# Cam_control.net
KiCad netlist of a schematic drawn in Altium Designer
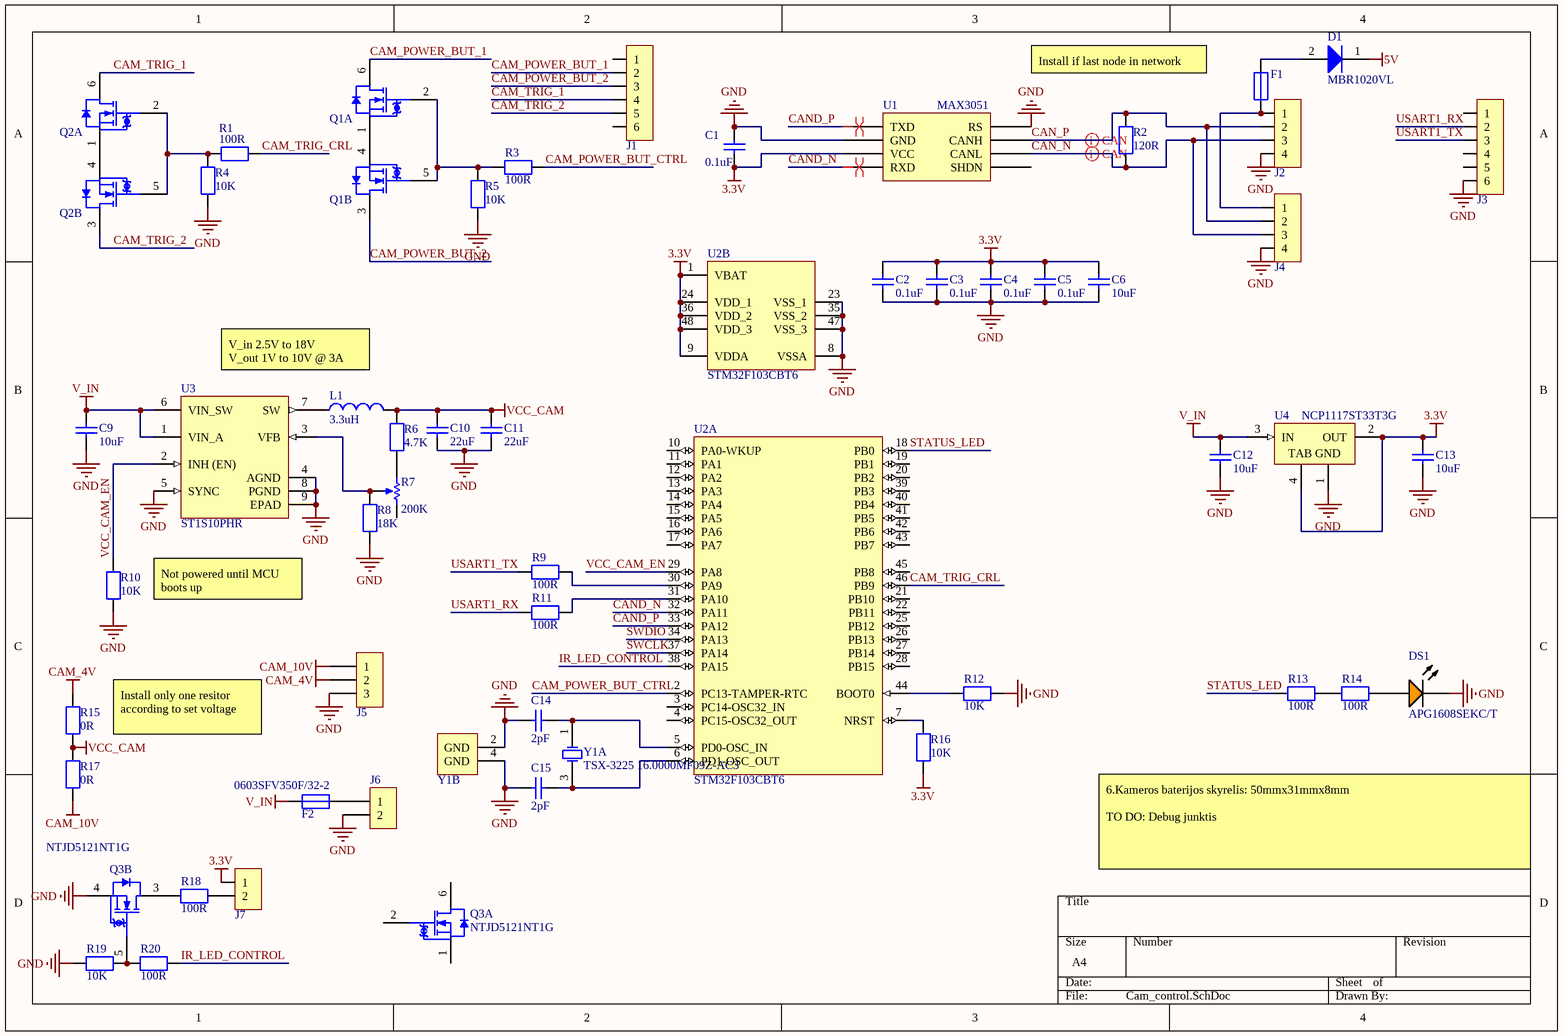
[diagram p0: Cam_control.SchDoc]

(export (version "E")
  (design (tool "Eeschema 10.0.6"))
  (components
    (comp (ref "C1")
      (value "0.1uF")
      (footprint "0603_CAP")
      (fields (field (name "Comment") "Capacitor"))
      (libsource (lib "Passive_comp") (part "Capacitor"))
    )
    (comp (ref "C2")
      (value "0.1uF")
      (footprint "0603_CAP")
      (fields (field (name "Comment") "Capacitor"))
      (libsource (lib "Passive_comp") (part "Capacitor"))
    )
    (comp (ref "C3")
      (value "0.1uF")
      (footprint "0603_CAP")
      (fields (field (name "Comment") "Capacitor"))
      (libsource (lib "Passive_comp") (part "Capacitor"))
    )
    (comp (ref "C4")
      (value "0.1uF")
      (footprint "0603_CAP")
      (fields (field (name "Comment") "Capacitor"))
      (libsource (lib "Passive_comp") (part "Capacitor"))
    )
    (comp (ref "C5")
      (value "0.1uF")
      (footprint "0603_CAP")
      (fields (field (name "Comment") "Capacitor"))
      (libsource (lib "Passive_comp") (part "Capacitor"))
    )
    (comp (ref "C6")
      (value "10uF")
      (footprint "1206_CAP")
      (fields (field (name "Comment") "Capacitor"))
      (libsource (lib "Passive_comp") (part "Capacitor"))
    )
    (comp (ref "C9")
      (value "10uF")
      (footprint "1206_CAP")
      (fields (field (name "Comment") "Capacitor"))
      (libsource (lib "Passive_comp") (part "Capacitor"))
    )
    (comp (ref "C10")
      (value "22uF")
      (footprint "0805_CAP")
      (fields (field (name "Comment") "Capacitor"))
      (libsource (lib "Passive_comp") (part "Capacitor"))
    )
    (comp (ref "C11")
      (value "22uF")
      (footprint "0805_CAP")
      (fields (field (name "Comment") "Capacitor"))
      (libsource (lib "Passive_comp") (part "Capacitor"))
    )
    (comp (ref "C12")
      (value "10uF")
      (footprint "1206_CAP")
      (fields (field (name "Comment") "Capacitor"))
      (libsource (lib "Passive_comp") (part "Capacitor"))
    )
    (comp (ref "C13")
      (value "10uF")
      (footprint "1206_CAP")
      (fields (field (name "Comment") "Capacitor"))
      (libsource (lib "Passive_comp") (part "Capacitor"))
    )
    (comp (ref "C14")
      (value "2pF")
      (footprint "0603_CAP")
      (fields (field (name "Comment") "Capacitor"))
      (libsource (lib "Passive_comp") (part "Capacitor"))
    )
    (comp (ref "C15")
      (value "2pF")
      (footprint "0603_CAP")
      (fields (field (name "Comment") "Capacitor"))
      (libsource (lib "Passive_comp") (part "Capacitor"))
    )
    (comp (ref "D1")
      (value "MBR1020VL")
      (footprint "SOD-123-2")
      (libsource (lib "Passive_comp") (part "Diode"))
    )
    (comp (ref "DS1")
      (value "APG1608SEKC/T")
      (footprint "KING-LED0603-25-ORANGE_V")
      (description "LED, SMT, 0603(1608), 0.25mm Tthickness, Super Bright Orange")
      (libsource (lib "Altium Content Vault") (part "KING-LED_ORANGE_A1K2-2"))
    )
    (comp (ref "F1") (value "Fuse") (footprint "0603_RES") (libsource (lib "Passive_comp") (part "Fuse")))
    (comp (ref "F2") (value "0603SFV350F/32-2") (footprint "0603_RES") (libsource (lib "") (part "Fuse_1")))
    (comp (ref "J1")
      (value "DF13-6P\n1.25mm Pitch Miniature Crimping Connector.")
      (footprint "DF13-6P-1.25DS")
      (libsource (lib "df13") (part "DF13-6P-1.25DS"))
    )
    (comp (ref "J2")
      (value "DF13-4P\n1.25mm Pitch Miniature Crimping Connector.")
      (footprint "DF13-4P-1.25DS")
      (libsource (lib "df13") (part "DF13-4P-1.25DS"))
    )
    (comp (ref "J3")
      (value "DF13-6P\n1.25mm Pitch Miniature Crimping Connector.")
      (footprint "DF13-6P-1.25DS")
      (libsource (lib "df13") (part "DF13-6P-1.25DS"))
    )
    (comp (ref "J4")
      (value "DF13-4P\n1.25mm Pitch Miniature Crimping Connector.")
      (footprint "DF13-4P-1.25DS")
      (libsource (lib "df13") (part "DF13-4P-1.25DS"))
    )
    (comp (ref "J5")
      (value "Molex - Micro-Fit 3.0 Series connector,  3.00mm (0.118\") pitch header, 3 positions.")
      (footprint "43650-0300")
      (libsource (lib "molex-micro-fit-3.0") (part "HEADER_POS3_?43650-0300"))
    )
    (comp (ref "J6")
      (value "Micro-Fit 3.0, 3.00mm pitch header")
      (footprint "43650-0200")
      (libsource (lib "con-molex-micro-fit-3_0") (part "HEADER_POS2_?43650-0200"))
    )
    (comp (ref "J7")
      (value "DF13-2P\n1.25mm Pitch Miniature Crimping Connector.")
      (footprint "DF13-2P-1.25DS")
      (libsource (lib "con-hirose-df13") (part "DF13-2P-1.25DS"))
    )
    (comp (ref "L1")
      (value "3.3uH")
      (footprint "ASPI0530")
      (fields (field (name "Comment") "Inductor"))
      (libsource (lib "Passive_comp") (part "Inductor"))
    )
    (comp (ref "Q1")
      (value "NTJD5121NT1G")
      (footprint "ONSC-SC70-6-419B-02_V")
      (description "Power MOSFET, 60 V, 295 mA, Dual N-Channel with ESD Protection, 6-Pin SC70, Pb-Free, Tape and Reel")
      (fields (field (name "MANUFACTURER") "On Semiconductor"))
      (libsource (lib "Altium Content Vault") (part "CMP-1058-00623-1"))
    )
    (comp (ref "Q2")
      (value "NTJD5121NT1G")
      (footprint "ONSC-SC70-6-419B-02_V")
      (description "Power MOSFET, 60 V, 295 mA, Dual N-Channel with ESD Protection, 6-Pin SC70, Pb-Free, Tape and Reel")
      (fields (field (name "MANUFACTURER") "On Semiconductor"))
      (libsource (lib "Altium Content Vault") (part "CMP-1058-00623-1"))
    )
    (comp (ref "Q3")
      (value "NTJD5121NT1G")
      (footprint "ONSC-SC70-6-419B-02_V")
      (description "Power MOSFET, 60 V, 295 mA, Dual N-Channel with ESD Protection, 6-Pin SC70, Pb-Free, Tape and Reel")
      (fields (field (name "MANUFACTURER") "On Semiconductor"))
      (libsource (lib "Altium Content Vault") (part "ONSC-NNMOS-6_G"))
    )
    (comp (ref "R1")
      (value "100R")
      (footprint "0603_RES")
      (fields (field (name "Comment") "Resitor"))
      (libsource (lib "Passive_comp") (part "Resitor"))
    )
    (comp (ref "R2")
      (value "120R")
      (footprint "0603_RES")
      (fields (field (name "Comment") "Resitor"))
      (libsource (lib "") (part "Resitor_1"))
    )
    (comp (ref "R3")
      (value "100R")
      (footprint "0603_RES")
      (fields (field (name "Comment") "Resitor"))
      (libsource (lib "Passive_comp") (part "Resitor"))
    )
    (comp (ref "R4")
      (value "10K")
      (footprint "0603_RES")
      (fields (field (name "Comment") "Resitor"))
      (libsource (lib "") (part "Resitor_1"))
    )
    (comp (ref "R5")
      (value "10K")
      (footprint "0603_RES")
      (fields (field (name "Comment") "Resitor"))
      (libsource (lib "") (part "Resitor_1"))
    )
    (comp (ref "R6")
      (value "4.7K")
      (footprint "0603_RES")
      (fields (field (name "Comment") "Resitor"))
      (libsource (lib "") (part "Resitor_1"))
    )
    (comp (ref "R7")
      (value "200K")
      (footprint "TC33X-2")
      (fields (field (name "Comment") "Potenciometer"))
      (libsource (lib "Passive_comp") (part "Potenciometer"))
    )
    (comp (ref "R8")
      (value "18K")
      (footprint "0603_RES")
      (fields (field (name "Comment") "Resitor"))
      (libsource (lib "") (part "Resitor_1"))
    )
    (comp (ref "R9")
      (value "100R")
      (footprint "0603_RES")
      (fields (field (name "Comment") "Resitor"))
      (libsource (lib "Passive_comp") (part "Resitor"))
    )
    (comp (ref "R10")
      (value "10K")
      (footprint "0603_RES")
      (fields (field (name "Comment") "Resitor"))
      (libsource (lib "") (part "Resitor_1"))
    )
    (comp (ref "R11")
      (value "100R")
      (footprint "0603_RES")
      (fields (field (name "Comment") "Resitor"))
      (libsource (lib "Passive_comp") (part "Resitor"))
    )
    (comp (ref "R12")
      (value "10K")
      (footprint "0603_RES")
      (fields (field (name "Comment") "Resitor"))
      (libsource (lib "") (part "Resitor_2"))
    )
    (comp (ref "R13")
      (value "100R")
      (footprint "0603_RES")
      (fields (field (name "Comment") "Resitor"))
      (libsource (lib "Passive_comp") (part "Resitor"))
    )
    (comp (ref "R14")
      (value "100R")
      (footprint "0603_RES")
      (fields (field (name "Comment") "Resitor"))
      (libsource (lib "Passive_comp") (part "Resitor"))
    )
    (comp (ref "R15")
      (value "0R")
      (footprint "0603_RES")
      (fields (field (name "Comment") "Resitor"))
      (libsource (lib "") (part "Resitor_1"))
    )
    (comp (ref "R16")
      (value "10K")
      (footprint "0603_RES")
      (fields (field (name "Comment") "Resitor"))
      (libsource (lib "") (part "Resitor_1"))
    )
    (comp (ref "R17")
      (value "0R")
      (footprint "0603_RES")
      (fields (field (name "Comment") "Resitor"))
      (libsource (lib "") (part "Resitor_1"))
    )
    (comp (ref "R18")
      (value "100R")
      (footprint "0603_RES")
      (fields (field (name "Comment") "Resitor"))
      (libsource (lib "Passive_comp") (part "Resitor"))
    )
    (comp (ref "R19")
      (value "10K")
      (footprint "0603_RES")
      (fields (field (name "Comment") "Resitor"))
      (libsource (lib "") (part "Resitor_2"))
    )
    (comp (ref "R20")
      (value "100R")
      (footprint "0603_RES")
      (fields (field (name "Comment") "Resitor"))
      (libsource (lib "Passive_comp") (part "Resitor"))
    )
    (comp (ref "U1")
      (value "MAX3051")
      (footprint "SOIC127P600X175-8M")
      (libsource (lib "Active_comp") (part "MAX3051"))
    )
    (comp (ref "U2")
      (value "STM32F103CBT6")
      (footprint "STM-LQFP48_L")
      (libsource (lib "Altium Content Vault") (part "MC-ARM-STM32F103X8_B-SQ48"))
    )
    (comp (ref "U3")
      (value "ST1S10PHR")
      (footprint "HSO-8_L")
      (description "Monolithic synchronous step-down regulator, 8-Pin HSOP, Tape and Reel")
      (libsource (lib "Altium Content Vault") (part "PM-REG-ST1S10-IL9"))
    )
    (comp (ref "U4")
      (value "NCP1117ST33T3G")
      (footprint "ONSC-SOT-223_M")
      (fields (field (name "MANUFACTURER") "ON Semiconductor"))
      (libsource (lib "Altium Content Vault") (part "CMP-0592-00001-1"))
    )
    (comp (ref "Y1")
      (value "TSX-3225 16.0000MF09Z-AC3")
      (footprint "TSX-3225")
      (libsource (lib "") (part "TSX-3225 16.0000MF09Z-AC3_1"))
    )
  )
  (nets
    (net (code "1") (name "/CAM_POWER_BUT_1") (class "Default")
      (node (ref "J1") (pin "2") (pinfunction "2_2") (pintype "passive"))
      (node (ref "Q1") (pin "6") (pinfunction "D1_6") (pintype "passive"))
    )
    (net (code "2") (name "/CAM_POWER_BUT_2") (class "Default")
      (node (ref "J1") (pin "3") (pinfunction "3_3") (pintype "passive"))
      (node (ref "Q1") (pin "3") (pinfunction "D2_3") (pintype "passive"))
    )
    (net (code "3") (name "/CAM_POWER_BUT_CTRL") (class "Default")
      (node (ref "R3") (pin "2") (pinfunction "2_2") (pintype "passive"))
      (node (ref "U2") (pin "2") (pinfunction "PC13-TAMPER-RTC_2") (pintype "bidirectional"))
    )
    (net (code "4") (name "/CAM_TRIG_1") (class "Default")
      (node (ref "J1") (pin "4") (pinfunction "4_4") (pintype "passive"))
      (node (ref "Q2") (pin "6") (pinfunction "D1_6") (pintype "passive"))
    )
    (net (code "5") (name "/CAM_TRIG_2") (class "Default")
      (node (ref "J1") (pin "5") (pinfunction "5_5") (pintype "passive"))
      (node (ref "Q2") (pin "3") (pinfunction "D2_3") (pintype "passive"))
    )
    (net (code "6") (name "/CAM_TRIG_CRL") (class "Default")
      (node (ref "R1") (pin "2") (pinfunction "2_2") (pintype "passive"))
      (node (ref "U2") (pin "46") (pinfunction "PB9_46") (pintype "bidirectional"))
    )
    (net (code "7") (name "/CAND_N") (class "Default")
      (node (ref "U1") (pin "4") (pinfunction "RXD_4") (pintype "passive"))
      (node (ref "U2") (pin "32") (pinfunction "PA11_32") (pintype "bidirectional"))
    )
    (net (code "8") (name "/CAND_P") (class "Default")
      (node (ref "U1") (pin "1") (pinfunction "TXD_1") (pintype "passive"))
      (node (ref "U2") (pin "33") (pinfunction "PA12_33") (pintype "bidirectional"))
    )
    (net (code "9") (name "/CAN_N") (class "Default")
      (node (ref "J2") (pin "3") (pinfunction "3_3") (pintype "passive"))
      (node (ref "J4") (pin "3") (pinfunction "3_3") (pintype "passive"))
      (node (ref "R2") (pin "1") (pinfunction "1_1") (pintype "passive"))
      (node (ref "U1") (pin "6") (pinfunction "CANL_6") (pintype "passive"))
    )
    (net (code "10") (name "/CAN_P") (class "Default")
      (node (ref "J2") (pin "2") (pinfunction "2_2") (pintype "passive"))
      (node (ref "J4") (pin "2") (pinfunction "2_2") (pintype "passive"))
      (node (ref "R2") (pin "2") (pinfunction "2_2") (pintype "passive"))
      (node (ref "U1") (pin "7") (pinfunction "CANH_7") (pintype "passive"))
    )
    (net (code "11") (name "/IR_LED_CONTROL") (class "Default")
      (node (ref "R20") (pin "2") (pinfunction "2_2") (pintype "passive"))
      (node (ref "U2") (pin "38") (pinfunction "PA15_38") (pintype "bidirectional"))
    )
    (net (code "12") (name "/STATUS_LED") (class "Default")
      (node (ref "R13") (pin "1") (pinfunction "1_1") (pintype "passive"))
      (node (ref "U2") (pin "18") (pinfunction "PB0_18") (pintype "bidirectional"))
    )
    (net (code "13") (name "/SWCLK") (class "Default")
      (node (ref "U2") (pin "37") (pinfunction "PA14_37") (pintype "bidirectional"))
    )
    (net (code "14") (name "/SWDIO") (class "Default")
      (node (ref "U2") (pin "34") (pinfunction "PA13_34") (pintype "bidirectional"))
    )
    (net (code "15") (name "/USART1_RX") (class "Default")
      (node (ref "J3") (pin "2") (pinfunction "2_2") (pintype "passive"))
      (node (ref "R11") (pin "1") (pinfunction "1_1") (pintype "passive"))
    )
    (net (code "16") (name "/USART1_TX") (class "Default")
      (node (ref "J3") (pin "3") (pinfunction "3_3") (pintype "passive"))
      (node (ref "R9") (pin "1") (pinfunction "1_1") (pintype "passive"))
    )
    (net (code "17") (name "/VCC_CAM_EN") (class "Default")
      (node (ref "R10") (pin "2") (pinfunction "2_2") (pintype "passive"))
      (node (ref "U2") (pin "29") (pinfunction "PA8_29") (pintype "bidirectional"))
      (node (ref "U3") (pin "2") (pinfunction "INH_(EN)_2") (pintype "input"))
    )
    (net (code "18") (name "3.3V") (class "Default")
      (node (ref "C1") (pin "1") (pinfunction "1_1") (pintype "passive"))
      (node (ref "C13") (pin "2") (pinfunction "2_2") (pintype "passive"))
      (node (ref "C2") (pin "2") (pinfunction "2_2") (pintype "passive"))
      (node (ref "C3") (pin "2") (pinfunction "2_2") (pintype "passive"))
      (node (ref "C4") (pin "2") (pinfunction "2_2") (pintype "passive"))
      (node (ref "C5") (pin "2") (pinfunction "2_2") (pintype "passive"))
      (node (ref "C6") (pin "2") (pinfunction "2_2") (pintype "passive"))
      (node (ref "J7") (pin "1") (pinfunction "1_1") (pintype "passive"))
      (node (ref "R16") (pin "1") (pinfunction "1_1") (pintype "passive"))
      (node (ref "U1") (pin "3") (pinfunction "VCC_3") (pintype "passive"))
      (node (ref "U2") (pin "1") (pinfunction "VBAT_1") (pintype "power_in"))
      (node (ref "U2") (pin "24") (pinfunction "VDD_1_24") (pintype "power_in"))
      (node (ref "U2") (pin "36") (pinfunction "VDD_2_36") (pintype "power_in"))
      (node (ref "U2") (pin "48") (pinfunction "VDD_3_48") (pintype "power_in"))
      (node (ref "U2") (pin "9") (pinfunction "VDDA_9") (pintype "power_in"))
      (node (ref "U4") (pin "2") (pinfunction "OUT_2") (pintype "power_in"))
      (node (ref "U4") (pin "4") (pinfunction "TAB_4") (pintype "power_in"))
    )
    (net (code "19") (name "5V") (class "Default")
      (node (ref "D1") (pin "1") (pinfunction "K_1") (pintype "passive"))
    )
    (net (code "20") (name "CAM_4V") (class "Default")
      (node (ref "J5") (pin "2") (pinfunction "2_2") (pintype "passive"))
      (node (ref "R15") (pin "2") (pinfunction "2_2") (pintype "passive"))
    )
    (net (code "21") (name "CAM_10V") (class "Default")
      (node (ref "J5") (pin "1") (pinfunction "1_1") (pintype "passive"))
      (node (ref "R17") (pin "1") (pinfunction "1_1") (pintype "passive"))
    )
    (net (code "22") (name "GND") (class "Default")
      (node (ref "C1") (pin "2") (pinfunction "2_2") (pintype "passive"))
      (node (ref "C10") (pin "1") (pinfunction "1_1") (pintype "passive"))
      (node (ref "C11") (pin "1") (pinfunction "1_1") (pintype "passive"))
      (node (ref "C12") (pin "1") (pinfunction "1_1") (pintype "passive"))
      (node (ref "C13") (pin "1") (pinfunction "1_1") (pintype "passive"))
      (node (ref "C14") (pin "1") (pinfunction "1_1") (pintype "passive"))
      (node (ref "C15") (pin "1") (pinfunction "1_1") (pintype "passive"))
      (node (ref "C2") (pin "1") (pinfunction "1_1") (pintype "passive"))
      (node (ref "C3") (pin "1") (pinfunction "1_1") (pintype "passive"))
      (node (ref "C4") (pin "1") (pinfunction "1_1") (pintype "passive"))
      (node (ref "C5") (pin "1") (pinfunction "1_1") (pintype "passive"))
      (node (ref "C6") (pin "1") (pinfunction "1_1") (pintype "passive"))
      (node (ref "C9") (pin "1") (pinfunction "1_1") (pintype "passive"))
      (node (ref "DS1") (pin "2") (pinfunction "K_2") (pintype "passive"))
      (node (ref "J2") (pin "4") (pinfunction "4_4") (pintype "passive"))
      (node (ref "J3") (pin "6") (pinfunction "6_6") (pintype "passive"))
      (node (ref "J4") (pin "4") (pinfunction "4_4") (pintype "passive"))
      (node (ref "J5") (pin "3") (pinfunction "3_3") (pintype "passive"))
      (node (ref "J6") (pin "2") (pinfunction "2_2") (pintype "passive"))
      (node (ref "Q3") (pin "4") (pinfunction "S2_4") (pintype "passive"))
      (node (ref "R10") (pin "1") (pinfunction "1_1") (pintype "passive"))
      (node (ref "R12") (pin "1") (pinfunction "1_1") (pintype "passive"))
      (node (ref "R19") (pin "2") (pinfunction "2_2") (pintype "passive"))
      (node (ref "R4") (pin "1") (pinfunction "1_1") (pintype "passive"))
      (node (ref "R5") (pin "1") (pinfunction "1_1") (pintype "passive"))
      (node (ref "R8") (pin "1") (pinfunction "1_1") (pintype "passive"))
      (node (ref "U1") (pin "2") (pinfunction "GND_2") (pintype "passive"))
      (node (ref "U1") (pin "8") (pinfunction "RS_8") (pintype "passive"))
      (node (ref "U2") (pin "23") (pinfunction "VSS_1_23") (pintype "power_in"))
      (node (ref "U2") (pin "35") (pinfunction "VSS_2_35") (pintype "power_in"))
      (node (ref "U2") (pin "47") (pinfunction "VSS_3_47") (pintype "power_in"))
      (node (ref "U2") (pin "8") (pinfunction "VSSA_8") (pintype "power_in"))
      (node (ref "U3") (pin "4") (pinfunction "AGND_4") (pintype "power_in"))
      (node (ref "U3") (pin "5") (pinfunction "SYNC_5") (pintype "input"))
      (node (ref "U3") (pin "8") (pinfunction "PGND_8") (pintype "power_in"))
      (node (ref "U3") (pin "9") (pinfunction "EPAD_9") (pintype "power_in"))
      (node (ref "U4") (pin "1") (pinfunction "GND_1") (pintype "power_in"))
      (node (ref "Y1") (pin "2") (pinfunction "GND_2") (pintype "power_in"))
      (node (ref "Y1") (pin "4") (pinfunction "GND_4") (pintype "power_in"))
    )
    (net (code "23") (name "Net-(D1-A)") (class "Default")
      (node (ref "D1") (pin "2") (pinfunction "A_2") (pintype "passive"))
      (node (ref "F1") (pin "2") (pinfunction "2_2") (pintype "passive"))
    )
    (net (code "24") (name "Net-(DS1-A)") (class "Default")
      (node (ref "DS1") (pin "1") (pinfunction "A_1") (pintype "passive"))
      (node (ref "R14") (pin "2") (pinfunction "2_2") (pintype "passive"))
    )
    (net (code "25") (name "Net-(F1-Pad1)") (class "Default")
      (node (ref "F1") (pin "1") (pinfunction "1_1") (pintype "passive"))
      (node (ref "J2") (pin "1") (pinfunction "1_1") (pintype "passive"))
      (node (ref "J4") (pin "1") (pinfunction "1_1") (pintype "passive"))
    )
    (net (code "26") (name "Net-(F2-Pad2)") (class "Default")
      (node (ref "F2") (pin "2") (pinfunction "2_2") (pintype "passive"))
      (node (ref "J6") (pin "1") (pinfunction "1_1") (pintype "passive"))
    )
    (net (code "27") (name "Net-(J7-Pad2)") (class "Default")
      (node (ref "J7") (pin "2") (pinfunction "2_2") (pintype "passive"))
      (node (ref "R18") (pin "2") (pinfunction "2_2") (pintype "passive"))
    )
    (net (code "28") (name "Net-(Q1A-G1)") (class "Default")
      (node (ref "Q1") (pin "2") (pinfunction "G1_2") (pintype "passive"))
      (node (ref "Q1") (pin "5") (pinfunction "G2_5") (pintype "passive"))
      (node (ref "R3") (pin "1") (pinfunction "1_1") (pintype "passive"))
      (node (ref "R5") (pin "2") (pinfunction "2_2") (pintype "passive"))
    )
    (net (code "29") (name "Net-(Q1A-S1)") (class "Default")
      (node (ref "Q1") (pin "1") (pinfunction "S1_1") (pintype "passive"))
      (node (ref "Q1") (pin "4") (pinfunction "S2_4") (pintype "passive"))
    )
    (net (code "30") (name "Net-(Q2A-G1)") (class "Default")
      (node (ref "Q2") (pin "2") (pinfunction "G1_2") (pintype "passive"))
      (node (ref "Q2") (pin "5") (pinfunction "G2_5") (pintype "passive"))
      (node (ref "R1") (pin "1") (pinfunction "1_1") (pintype "passive"))
      (node (ref "R4") (pin "2") (pinfunction "2_2") (pintype "passive"))
    )
    (net (code "31") (name "Net-(Q2A-S1)") (class "Default")
      (node (ref "Q2") (pin "1") (pinfunction "S1_1") (pintype "passive"))
      (node (ref "Q2") (pin "4") (pinfunction "S2_4") (pintype "passive"))
    )
    (net (code "32") (name "Net-(Q3B-D2)") (class "Default")
      (node (ref "Q3") (pin "3") (pinfunction "D2_3") (pintype "passive"))
      (node (ref "R18") (pin "1") (pinfunction "1_1") (pintype "passive"))
    )
    (net (code "33") (name "Net-(Q3B-G2)") (class "Default")
      (node (ref "Q3") (pin "5") (pinfunction "G2_5") (pintype "passive"))
      (node (ref "R19") (pin "1") (pinfunction "1_1") (pintype "passive"))
      (node (ref "R20") (pin "1") (pinfunction "1_1") (pintype "passive"))
    )
    (net (code "34") (name "Net-(R7-CCW)") (class "Default")
      (node (ref "R6") (pin "1") (pinfunction "1_1") (pintype "passive"))
      (node (ref "R7") (pin "1") (pinfunction "CCW_1") (pintype "passive"))
    )
    (net (code "35") (name "Net-(R7-WIPER)") (class "Default")
      (node (ref "R7") (pin "2") (pinfunction "WIPER_2") (pintype "passive"))
      (node (ref "R8") (pin "2") (pinfunction "2_2") (pintype "passive"))
      (node (ref "U3") (pin "3") (pinfunction "VFB_3") (pintype "input"))
    )
    (net (code "36") (name "Net-(R13-Pad2)") (class "Default")
      (node (ref "R13") (pin "2") (pinfunction "2_2") (pintype "passive"))
      (node (ref "R14") (pin "1") (pinfunction "1_1") (pintype "passive"))
    )
    (net (code "37") (name "Net-(U2A-BOOT0)") (class "Default")
      (node (ref "R12") (pin "2") (pinfunction "2_2") (pintype "passive"))
      (node (ref "U2") (pin "44") (pinfunction "BOOT0_44") (pintype "input"))
    )
    (net (code "38") (name "Net-(U2A-NRST)") (class "Default")
      (node (ref "R16") (pin "2") (pinfunction "2_2") (pintype "passive"))
      (node (ref "U2") (pin "7") (pinfunction "NRST_7") (pintype "bidirectional"))
    )
    (net (code "39") (name "Net-(U2A-PA9)") (class "Default")
      (node (ref "R9") (pin "2") (pinfunction "2_2") (pintype "passive"))
      (node (ref "U2") (pin "30") (pinfunction "PA9_30") (pintype "bidirectional"))
    )
    (net (code "40") (name "Net-(U2A-PA10)") (class "Default")
      (node (ref "R11") (pin "2") (pinfunction "2_2") (pintype "passive"))
      (node (ref "U2") (pin "31") (pinfunction "PA10_31") (pintype "bidirectional"))
    )
    (net (code "41") (name "Net-(U2A-PD0-OSC_IN)") (class "Default")
      (node (ref "C14") (pin "2") (pinfunction "2_2") (pintype "passive"))
      (node (ref "U2") (pin "5") (pinfunction "PD0-OSC_IN_5") (pintype "bidirectional"))
      (node (ref "Y1") (pin "1") (pinfunction "X1_1") (pintype "passive"))
    )
    (net (code "42") (name "Net-(U2A-PD1-OSC_OUT)") (class "Default")
      (node (ref "C15") (pin "2") (pinfunction "2_2") (pintype "passive"))
      (node (ref "U2") (pin "6") (pinfunction "PD1-OSC_OUT_6") (pintype "bidirectional"))
      (node (ref "Y1") (pin "3") (pinfunction "X2_3") (pintype "passive"))
    )
    (net (code "43") (name "Net-(U3-SW)") (class "Default")
      (node (ref "L1") (pin "1") (pinfunction "1_1") (pintype "passive"))
      (node (ref "U3") (pin "7") (pinfunction "SW_7") (pintype "output"))
    )
    (net (code "44") (name "VCC_CAM") (class "Default")
      (node (ref "C10") (pin "2") (pinfunction "2_2") (pintype "passive"))
      (node (ref "C11") (pin "2") (pinfunction "2_2") (pintype "passive"))
      (node (ref "L1") (pin "2") (pinfunction "2_2") (pintype "passive"))
      (node (ref "R15") (pin "1") (pinfunction "1_1") (pintype "passive"))
      (node (ref "R17") (pin "2") (pinfunction "2_2") (pintype "passive"))
      (node (ref "R6") (pin "2") (pinfunction "2_2") (pintype "passive"))
    )
    (net (code "45") (name "V_IN") (class "Default")
      (node (ref "C12") (pin "2") (pinfunction "2_2") (pintype "passive"))
      (node (ref "C9") (pin "2") (pinfunction "2_2") (pintype "passive"))
      (node (ref "F2") (pin "1") (pinfunction "1_1") (pintype "passive"))
      (node (ref "U3") (pin "1") (pinfunction "VIN_A_1") (pintype "power_in"))
      (node (ref "U3") (pin "6") (pinfunction "VIN_SW_6") (pintype "power_in"))
      (node (ref "U4") (pin "3") (pinfunction "IN_3") (pintype "input"))
    )
    (net (code "46") (name "unconnected-(J1-Pad1)") (class "Default")
      (node (ref "J1") (pin "1") (pinfunction "1_1") (pintype "passive"))
    )
    (net (code "47") (name "unconnected-(J1-Pad6)") (class "Default")
      (node (ref "J1") (pin "6") (pinfunction "6_6") (pintype "passive"))
    )
    (net (code "48") (name "unconnected-(J3-Pad1)") (class "Default")
      (node (ref "J3") (pin "1") (pinfunction "1_1") (pintype "passive"))
    )
    (net (code "49") (name "unconnected-(J3-Pad4)") (class "Default")
      (node (ref "J3") (pin "4") (pinfunction "4_4") (pintype "passive"))
    )
    (net (code "50") (name "unconnected-(J3-Pad5)") (class "Default")
      (node (ref "J3") (pin "5") (pinfunction "5_5") (pintype "passive"))
    )
    (net (code "51") (name "unconnected-(Q3A-D1-Pad6)") (class "Default")
      (node (ref "Q3") (pin "6") (pinfunction "D1_6") (pintype "passive"))
    )
    (net (code "52") (name "unconnected-(Q3A-G1-Pad2)") (class "Default")
      (node (ref "Q3") (pin "2") (pinfunction "G1_2") (pintype "passive"))
    )
    (net (code "53") (name "unconnected-(Q3A-S1-Pad1)") (class "Default")
      (node (ref "Q3") (pin "1") (pinfunction "S1_1") (pintype "passive"))
    )
    (net (code "54") (name "unconnected-(R7-CW-Pad3)") (class "Default")
      (node (ref "R7") (pin "3") (pinfunction "CW_3") (pintype "passive"))
    )
    (net (code "55") (name "unconnected-(U1-SHDN-Pad5)") (class "Default")
      (node (ref "U1") (pin "5") (pinfunction "SHDN_5") (pintype "passive"))
    )
    (net (code "56") (name "unconnected-(U2A-PA0-WKUP-Pad10)") (class "Default")
      (node (ref "U2") (pin "10") (pinfunction "PA0-WKUP_10") (pintype "bidirectional"))
    )
    (net (code "57") (name "unconnected-(U2A-PA1-Pad11)") (class "Default")
      (node (ref "U2") (pin "11") (pinfunction "PA1_11") (pintype "bidirectional"))
    )
    (net (code "58") (name "unconnected-(U2A-PA2-Pad12)") (class "Default")
      (node (ref "U2") (pin "12") (pinfunction "PA2_12") (pintype "bidirectional"))
    )
    (net (code "59") (name "unconnected-(U2A-PA3-Pad13)") (class "Default")
      (node (ref "U2") (pin "13") (pinfunction "PA3_13") (pintype "bidirectional"))
    )
    (net (code "60") (name "unconnected-(U2A-PA4-Pad14)") (class "Default")
      (node (ref "U2") (pin "14") (pinfunction "PA4_14") (pintype "bidirectional"))
    )
    (net (code "61") (name "unconnected-(U2A-PA5-Pad15)") (class "Default")
      (node (ref "U2") (pin "15") (pinfunction "PA5_15") (pintype "bidirectional"))
    )
    (net (code "62") (name "unconnected-(U2A-PA6-Pad16)") (class "Default")
      (node (ref "U2") (pin "16") (pinfunction "PA6_16") (pintype "bidirectional"))
    )
    (net (code "63") (name "unconnected-(U2A-PA7-Pad17)") (class "Default")
      (node (ref "U2") (pin "17") (pinfunction "PA7_17") (pintype "bidirectional"))
    )
    (net (code "64") (name "unconnected-(U2A-PB1-Pad19)") (class "Default")
      (node (ref "U2") (pin "19") (pinfunction "PB1_19") (pintype "bidirectional"))
    )
    (net (code "65") (name "unconnected-(U2A-PB2-Pad20)") (class "Default")
      (node (ref "U2") (pin "20") (pinfunction "PB2_20") (pintype "bidirectional"))
    )
    (net (code "66") (name "unconnected-(U2A-PB3-Pad39)") (class "Default")
      (node (ref "U2") (pin "39") (pinfunction "PB3_39") (pintype "bidirectional"))
    )
    (net (code "67") (name "unconnected-(U2A-PB4-Pad40)") (class "Default")
      (node (ref "U2") (pin "40") (pinfunction "PB4_40") (pintype "bidirectional"))
    )
    (net (code "68") (name "unconnected-(U2A-PB5-Pad41)") (class "Default")
      (node (ref "U2") (pin "41") (pinfunction "PB5_41") (pintype "bidirectional"))
    )
    (net (code "69") (name "unconnected-(U2A-PB6-Pad42)") (class "Default")
      (node (ref "U2") (pin "42") (pinfunction "PB6_42") (pintype "bidirectional"))
    )
    (net (code "70") (name "unconnected-(U2A-PB7-Pad43)") (class "Default")
      (node (ref "U2") (pin "43") (pinfunction "PB7_43") (pintype "bidirectional"))
    )
    (net (code "71") (name "unconnected-(U2A-PB8-Pad45)") (class "Default")
      (node (ref "U2") (pin "45") (pinfunction "PB8_45") (pintype "bidirectional"))
    )
    (net (code "72") (name "unconnected-(U2A-PB10-Pad21)") (class "Default")
      (node (ref "U2") (pin "21") (pinfunction "PB10_21") (pintype "bidirectional"))
    )
    (net (code "73") (name "unconnected-(U2A-PB11-Pad22)") (class "Default")
      (node (ref "U2") (pin "22") (pinfunction "PB11_22") (pintype "bidirectional"))
    )
    (net (code "74") (name "unconnected-(U2A-PB12-Pad25)") (class "Default")
      (node (ref "U2") (pin "25") (pinfunction "PB12_25") (pintype "bidirectional"))
    )
    (net (code "75") (name "unconnected-(U2A-PB13-Pad26)") (class "Default")
      (node (ref "U2") (pin "26") (pinfunction "PB13_26") (pintype "bidirectional"))
    )
    (net (code "76") (name "unconnected-(U2A-PB14-Pad27)") (class "Default")
      (node (ref "U2") (pin "27") (pinfunction "PB14_27") (pintype "bidirectional"))
    )
    (net (code "77") (name "unconnected-(U2A-PB15-Pad28)") (class "Default")
      (node (ref "U2") (pin "28") (pinfunction "PB15_28") (pintype "bidirectional"))
    )
    (net (code "78") (name "unconnected-(U2A-PC14-OSC32_IN-Pad3)") (class "Default")
      (node (ref "U2") (pin "3") (pinfunction "PC14-OSC32_IN_3") (pintype "bidirectional"))
    )
    (net (code "79") (name "unconnected-(U2A-PC15-OSC32_OUT-Pad4)") (class "Default")
      (node (ref "U2") (pin "4") (pinfunction "PC15-OSC32_OUT_4") (pintype "bidirectional"))
    )
  )
)
